# Buzzer.net
KiCad netlist of a schematic drawn in Altium Designer
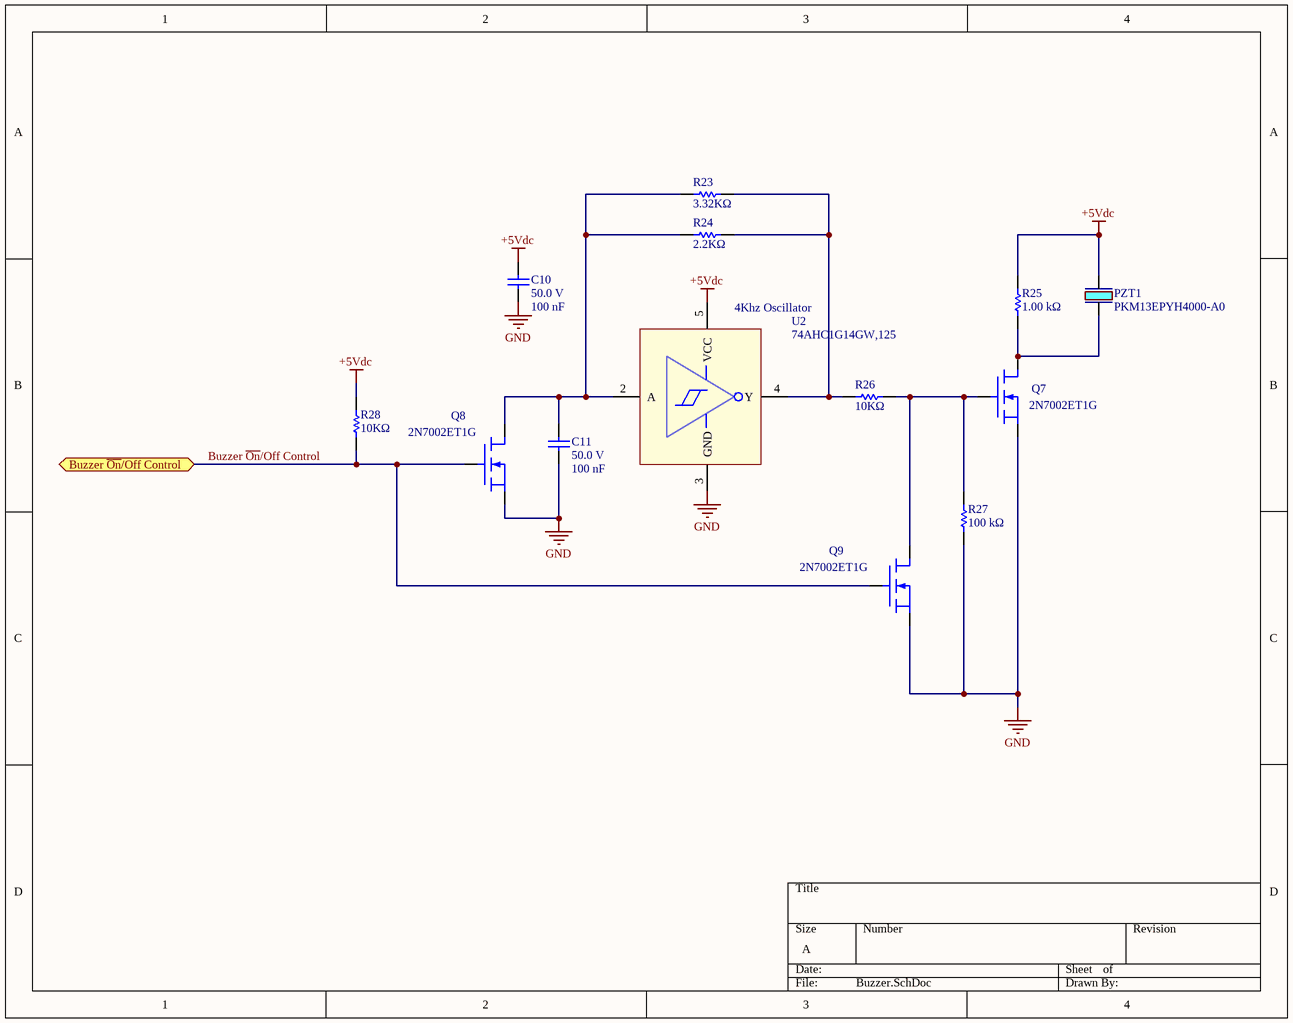
[diagram p0: Buzzer.SchDoc]

(export (version "E")
  (design (tool "Eeschema 10.0.6"))
  (components
    (comp (ref "C10")
      (value "08055C104JAT2A")
      (footprint "Cap,0805")
      (description "Capacitor; Ceramic; Cap 0.1 uF; Tol 5%; Vol-Rtg 50 VDC; SMT; 0805; X7R; Tape & Reel")
      (fields (field (name "VOLTAGE RATING (DC)") "50.0 V") (field (name "CAPACITANCE") "100 nF"))
      (libsource (lib "Master Mar2021") (part "Cap,0805,100nf,50V,5%,08055C104JAT2A"))
    )
    (comp (ref "C11")
      (value "08055C104JAT2A")
      (footprint "Cap,0805")
      (description "Capacitor; Ceramic; Cap 0.1 uF; Tol 5%; Vol-Rtg 50 VDC; SMT; 0805; X7R; Tape & Reel")
      (fields (field (name "VOLTAGE RATING (DC)") "50.0 V") (field (name "CAPACITANCE") "100 nF"))
      (libsource (lib "Master Mar2021") (part "Cap,0805,100nf,50V,5%,08055C104JAT2A"))
    )
    (comp (ref "PZT1")
      (value "PKM13EPYH4000-A0")
      (footprint "Buzzer,PKM13EPYH4000-A0")
      (description "AUDIO PIEZO TRANSDUCER 30V TH")
      (fields (field (name "MANUFACTURER") "Murata Electronics"))
      (libsource (lib "Master Mar2021") (part "Buzzer,PIEZO,30V,TH,4Khz,PKM13EPYH4000-A0"))
    )
    (comp (ref "Q7")
      (value "2N7002ET1G")
      (footprint "SOT23-3")
      (description "Small Signal MOSFET, 60 V, 310 mA, Single, N-Channel, 3-Pin SOT-23, Pb-Free, Tape and Reel")
      (fields
        (field (name "MANUFACTURER") "ON Semiconductor")
        (field (name "MANUFACTURER PART NUMBER") "2N7002ET1G")
      )
      (libsource (lib "Master Mar2021") (part "MOSFET,N-Channel,SOT23,0.25A,60V,2N7002ET1G"))
    )
    (comp (ref "Q8")
      (value "2N7002ET1G")
      (footprint "SOT23-3")
      (description "Small Signal MOSFET, 60 V, 310 mA, Single, N-Channel, 3-Pin SOT-23, Pb-Free, Tape and Reel")
      (fields
        (field (name "MANUFACTURER") "ON Semiconductor")
        (field (name "MANUFACTURER PART NUMBER") "2N7002ET1G")
      )
      (libsource (lib "Master Mar2021") (part "MOSFET,N-Channel,SOT23,0.25A,60V,2N7002ET1G"))
    )
    (comp (ref "Q9")
      (value "2N7002ET1G")
      (footprint "SOT23-3")
      (description "Small Signal MOSFET, 60 V, 310 mA, Single, N-Channel, 3-Pin SOT-23, Pb-Free, Tape and Reel")
      (fields
        (field (name "MANUFACTURER") "ON Semiconductor")
        (field (name "MANUFACTURER PART NUMBER") "2N7002ET1G")
      )
      (libsource (lib "Master Mar2021") (part "MOSFET,N-Channel,SOT23,0.25A,60V,2N7002ET1G"))
    )
    (comp (ref "R23")
      (value "CRCW08053K32FKEA")
      (footprint "res, 0805, HD")
      (description "RES SMD 3.32K OHM 1% 1/8W 0805")
      (fields (field (name "RESISTANCE") "3.32KΩ"))
      (libsource (lib "Master Mar2021") (part "Res,0805,3.32K,±1%,100.0 ppm/°C,150.0 V,CRCW08053K32FKEA"))
    )
    (comp (ref "R24")
      (value "CRCW08052K20FKEA")
      (footprint "res, 0805, HD")
      (description "RES SMD 2.2K OHM 1% 1/8W 0805")
      (fields (field (name "RESISTANCE") "2.2KΩ"))
      (libsource (lib "Master Mar2021") (part "Res,0805,2.2KΩ,±1%,100.0 ppm/°C,150.0 V,CRCW08052K20FKEA"))
    )
    (comp (ref "R25")
      (value "Vishay CRCW08051K00JNEA")
      (footprint "res, 0805, HD")
      (description "Res Thick Film 0805 1K Ohm 5% 0.125W(1/8W) ±200ppm/C Molded SMD Automotive Paper T/R")
      (fields
        (field (name "MANUFACTURER PART NUMBER") "CRCW08051K00JNEA")
        (field (name "RESISTANCE") "1.00 kΩ")
      )
      (libsource (lib "Master Mar2021") (part "Res,0805,1.00 kΩ,5%,200ppm,CRCW08051K00JNEA"))
    )
    (comp (ref "R26")
      (value "Vishay / Dale CRCW080510K0FKTA")
      (footprint "res, 0805, HD")
      (description "RES SMD 10K OHM 1% 1/8W 0805")
      (fields (field (name "RESISTANCE") "10KΩ"))
      (libsource (lib "Master Mar2021") (part "Res,0805,10.0kΩ,1%,100 ppm,CRCW080510K0FKTA"))
    )
    (comp (ref "R27")
      (value "CRCW0805100KFKEA")
      (footprint "res, 0805, HD")
      (description "100 kOhms ±1% 0.125W, 1/8W Chip Resistor 0805 (2012 Metric) Thick Film")
      (fields (field (name "MANUFACTURER") "Vishay") (field (name "RESISTANCE") "100 kΩ"))
      (libsource (lib "Master Mar2021") (part "Res,0805,100kΩ,1%,100ppm,CRCW0805100KFKEA"))
    )
    (comp (ref "R28")
      (value "Vishay / Dale CRCW080510K0FKTA")
      (footprint "res, 0805, HD")
      (description "RES SMD 10K OHM 1% 1/8W 0805")
      (fields (field (name "RESISTANCE") "10KΩ"))
      (libsource (lib "Master Mar2021") (part "Res,0805,10.0kΩ,1%,100 ppm,CRCW080510K0FKTA"))
    )
    (comp (ref "U2")
      (value "74AHC1G14GW,125")
      (footprint "SOT-353")
      (description "IC INVERTER SCHMITT 1CH 5TSSOP")
      (fields (field (name "MANUFACTURER") "Nexperia USA Inc."))
      (libsource (lib "Master Nov2021") (part "IC,Logic,Schmitt trigger INV,2V ~ 5.5V,5-TSSOP , 74AHC1G14GW,125"))
    )
  )
  (nets
    (net (code "1") (name "+5Vdc") (class "Default")
      (node (ref "C10") (pin "2") (pinfunction "2_2") (pintype "passive"))
      (node (ref "PZT1") (pin "2") (pinfunction "2_2") (pintype "passive"))
      (node (ref "R25") (pin "1") (pinfunction "1_1") (pintype "passive"))
      (node (ref "R28") (pin "1") (pinfunction "1_1") (pintype "passive"))
      (node (ref "U2") (pin "5") (pinfunction "VCC_5") (pintype "passive"))
    )
    (net (code "2") (name "/Buzzer ~{On}{slash}Off Control") (class "Default")
      (node (ref "Q8") (pin "1") (pinfunction "G_1") (pintype "passive"))
      (node (ref "Q9") (pin "1") (pinfunction "G_1") (pintype "passive"))
      (node (ref "R28") (pin "2") (pinfunction "2_2") (pintype "passive"))
    )
    (net (code "3") (name "GND") (class "Default")
      (node (ref "C10") (pin "1") (pinfunction "1_1") (pintype "passive"))
      (node (ref "C11") (pin "2") (pinfunction "2_2") (pintype "passive"))
      (node (ref "Q7") (pin "2") (pinfunction "S_2") (pintype "passive"))
      (node (ref "Q8") (pin "2") (pinfunction "S_2") (pintype "passive"))
      (node (ref "Q9") (pin "2") (pinfunction "S_2") (pintype "passive"))
      (node (ref "R27") (pin "2") (pinfunction "2_2") (pintype "passive"))
      (node (ref "U2") (pin "3") (pinfunction "GND_3") (pintype "passive"))
    )
    (net (code "4") (name "Net-(Q7-D)") (class "Default")
      (node (ref "PZT1") (pin "1") (pinfunction "1_1") (pintype "passive"))
      (node (ref "Q7") (pin "3") (pinfunction "D_3") (pintype "passive"))
      (node (ref "R25") (pin "2") (pinfunction "2_2") (pintype "passive"))
    )
    (net (code "5") (name "Net-(Q7-G)") (class "Default")
      (node (ref "Q7") (pin "1") (pinfunction "G_1") (pintype "passive"))
      (node (ref "Q9") (pin "3") (pinfunction "D_3") (pintype "passive"))
      (node (ref "R26") (pin "1") (pinfunction "1_1") (pintype "passive"))
      (node (ref "R27") (pin "1") (pinfunction "1_1") (pintype "passive"))
    )
    (net (code "6") (name "Net-(Q8-D)") (class "Default")
      (node (ref "C11") (pin "1") (pinfunction "1_1") (pintype "passive"))
      (node (ref "Q8") (pin "3") (pinfunction "D_3") (pintype "passive"))
      (node (ref "R23") (pin "2") (pinfunction "2_2") (pintype "passive"))
      (node (ref "R24") (pin "2") (pinfunction "2_2") (pintype "passive"))
      (node (ref "U2") (pin "2") (pinfunction "A_2") (pintype "passive"))
    )
    (net (code "7") (name "Net-(U2-Y)") (class "Default")
      (node (ref "R23") (pin "1") (pinfunction "1_1") (pintype "passive"))
      (node (ref "R24") (pin "1") (pinfunction "1_1") (pintype "passive"))
      (node (ref "R26") (pin "2") (pinfunction "2_2") (pintype "passive"))
      (node (ref "U2") (pin "4") (pinfunction "Y_4") (pintype "passive"))
    )
    (net (code "8") (name "unconnected-(U2-N{slash}C-Pad1)") (class "Default")
      (node (ref "U2") (pin "1") (pinfunction "N/C_1") (pintype "passive"))
    )
  )
)
